# ch340_usb.net
KiCad netlist of a schematic drawn in EAGLE
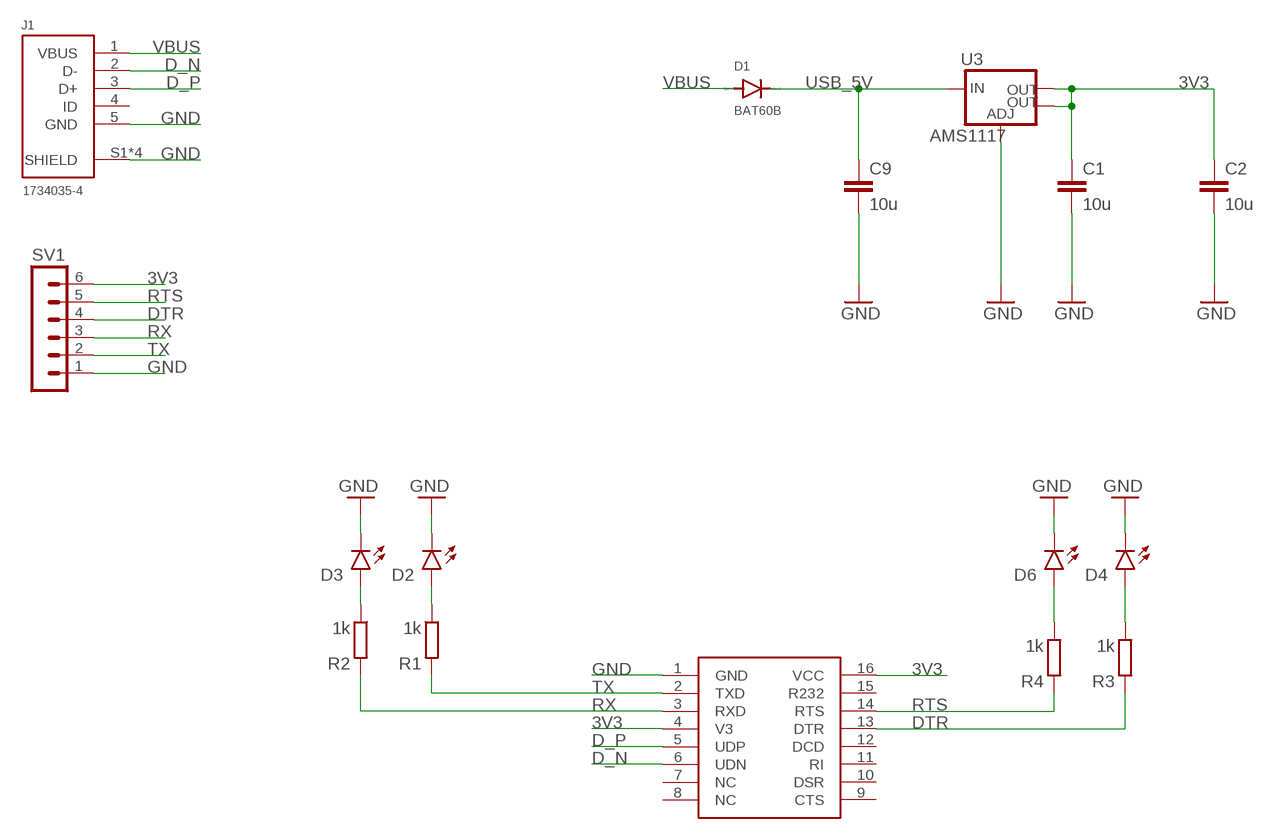
[diagram p0: schematic, sheet 1]

(export (version "E")
  (design (tool "Eeschema 10.0.6"))
  (components
    (comp (ref "C1")
      (value "10u")
      (footprint "eagle-import:C0805K")
      (libsource (lib "eagle-import") (part "C-EUC0805K"))
    )
    (comp (ref "C2")
      (value "10u")
      (footprint "eagle-import:C0805K")
      (libsource (lib "eagle-import") (part "C-EUC0805K"))
    )
    (comp (ref "C9")
      (value "10u")
      (footprint "eagle-import:C0805K")
      (libsource (lib "eagle-import") (part "C-EUC0805K"))
    )
    (comp (ref "D1")
      (value "BAT60B")
      (footprint "eagle-import:SOD123")
      (libsource (lib "eagle-import") (part "MBR0520LT"))
    )
    (comp (ref "D2")
      (value "PWR")
      (footprint "eagle-import:LED3MM")
      (fields (field (name "MF") "VISHAY SEMICONDUCTOR"))
      (libsource (lib "eagle-import") (part "TLLG4400"))
    )
    (comp (ref "D3")
      (value "PWR")
      (footprint "eagle-import:LED3MM")
      (fields (field (name "MF") "VISHAY SEMICONDUCTOR"))
      (libsource (lib "eagle-import") (part "TLLG4400"))
    )
    (comp (ref "D4")
      (value "PWR")
      (footprint "eagle-import:LED3MM")
      (fields (field (name "MF") "VISHAY SEMICONDUCTOR"))
      (libsource (lib "eagle-import") (part "TLLG4400"))
    )
    (comp (ref "D6")
      (value "PWR")
      (footprint "eagle-import:LED3MM")
      (fields (field (name "MF") "VISHAY SEMICONDUCTOR"))
      (libsource (lib "eagle-import") (part "TLLG4400"))
    )
    (comp (ref "J1")
      (value "1734035-4")
      (footprint "eagle-import:1734035-4")
      (fields
        (field (name "DIGIKEY_PARTNO") "A121554TR-ND")
        (field (name "MANUFACTURER") "TE Connectivity AMP Connectors")
        (field (name "CREATED_BY") "PCBLayout.com")
      )
      (libsource (lib "eagle-import") (part "1734035-4"))
    )
    (comp (ref "R1")
      (value "1k")
      (footprint "eagle-import:R0805")
      (libsource (lib "eagle-import") (part "R-EU_R0805"))
    )
    (comp (ref "R2")
      (value "1k")
      (footprint "eagle-import:R0805")
      (libsource (lib "eagle-import") (part "R-EU_R0805"))
    )
    (comp (ref "R3")
      (value "1k")
      (footprint "eagle-import:R0805")
      (libsource (lib "eagle-import") (part "R-EU_R0805"))
    )
    (comp (ref "R4")
      (value "1k")
      (footprint "eagle-import:R0805")
      (libsource (lib "eagle-import") (part "R-EU_R0805"))
    )
    (comp (ref "SV1")
      (value "MA06-1")
      (footprint "eagle-import:MA06-1")
      (libsource (lib "eagle-import") (part "MA06-1"))
    )
    (comp (ref "U$1")
      (value "CH340")
      (footprint "eagle-import:SOP16")
      (libsource (lib "eagle-import") (part "CH340"))
    )
    (comp (ref "U3")
      (value "AMS1117")
      (footprint "eagle-import:SOT223")
      (libsource (lib "eagle-import") (part "V_REG_LM1117SOT223"))
    )
  )
  (nets
    (net (code "1") (name "/3V3") (class "Default")
      (node (ref "C1") (pin "1") (pinfunction "1_1") (pintype "passive"))
      (node (ref "C2") (pin "1") (pinfunction "1_1") (pintype "passive"))
      (node (ref "SV1") (pin "6") (pinfunction "6_6") (pintype "passive"))
      (node (ref "U$1") (pin "16") (pinfunction "VCC_16") (pintype "bidirectional"))
      (node (ref "U$1") (pin "4") (pinfunction "V3_4") (pintype "bidirectional"))
      (node (ref "U3") (pin "2") (pinfunction "OUT_2") (pintype "output"))
      (node (ref "U3") (pin "4") (pinfunction "OUT_4") (pintype "output"))
    )
    (net (code "2") (name "/DTR") (class "Default")
      (node (ref "R3") (pin "2") (pinfunction "2_2") (pintype "passive"))
      (node (ref "SV1") (pin "4") (pinfunction "4_4") (pintype "passive"))
      (node (ref "U$1") (pin "13") (pinfunction "DTR_13") (pintype "bidirectional"))
    )
    (net (code "3") (name "/D_N") (class "Default")
      (node (ref "J1") (pin "2") (pinfunction "D-_2") (pintype "passive"))
      (node (ref "U$1") (pin "6") (pinfunction "UDN_6") (pintype "bidirectional"))
    )
    (net (code "4") (name "/D_P") (class "Default")
      (node (ref "J1") (pin "3") (pinfunction "D+_3") (pintype "passive"))
      (node (ref "U$1") (pin "5") (pinfunction "UDP_5") (pintype "bidirectional"))
    )
    (net (code "5") (name "/RTS") (class "Default")
      (node (ref "R4") (pin "2") (pinfunction "2_2") (pintype "passive"))
      (node (ref "SV1") (pin "5") (pinfunction "5_5") (pintype "passive"))
      (node (ref "U$1") (pin "14") (pinfunction "RTS_14") (pintype "bidirectional"))
    )
    (net (code "6") (name "/RX") (class "Default")
      (node (ref "R2") (pin "2") (pinfunction "2_2") (pintype "passive"))
      (node (ref "SV1") (pin "3") (pinfunction "3_3") (pintype "passive"))
      (node (ref "U$1") (pin "3") (pinfunction "RXD_3") (pintype "bidirectional"))
    )
    (net (code "7") (name "/TX") (class "Default")
      (node (ref "R1") (pin "2") (pinfunction "2_2") (pintype "passive"))
      (node (ref "SV1") (pin "2") (pinfunction "2_2") (pintype "passive"))
      (node (ref "U$1") (pin "2") (pinfunction "TXD_2") (pintype "bidirectional"))
    )
    (net (code "8") (name "/USB_5V") (class "Default")
      (node (ref "C9") (pin "1") (pinfunction "1_1") (pintype "passive"))
      (node (ref "D1") (pin "C") (pinfunction "C_C") (pintype "passive"))
      (node (ref "U3") (pin "3") (pinfunction "IN_3") (pintype "input"))
    )
    (net (code "9") (name "/VBUS") (class "Default")
      (node (ref "D1") (pin "A") (pinfunction "A_A") (pintype "passive"))
      (node (ref "J1") (pin "1") (pinfunction "VBUS_1") (pintype "passive"))
    )
    (net (code "10") (name "GND") (class "Default")
      (node (ref "C1") (pin "2") (pinfunction "2_2") (pintype "passive"))
      (node (ref "C2") (pin "2") (pinfunction "2_2") (pintype "passive"))
      (node (ref "C9") (pin "2") (pinfunction "2_2") (pintype "passive"))
      (node (ref "D2") (pin "K") (pinfunction "C_K") (pintype "passive"))
      (node (ref "D3") (pin "K") (pinfunction "C_K") (pintype "passive"))
      (node (ref "D4") (pin "K") (pinfunction "C_K") (pintype "passive"))
      (node (ref "D6") (pin "K") (pinfunction "C_K") (pintype "passive"))
      (node (ref "J1") (pin "5") (pinfunction "GND_5") (pintype "passive"))
      (node (ref "J1") (pin "S1") (pinfunction "SHIELD_S1") (pintype "power_in"))
      (node (ref "J1") (pin "S2") (pinfunction "SHIELD_S2") (pintype "power_in"))
      (node (ref "J1") (pin "S3") (pinfunction "SHIELD_S3") (pintype "power_in"))
      (node (ref "J1") (pin "S4") (pinfunction "SHIELD_S4") (pintype "power_in"))
      (node (ref "SV1") (pin "1") (pinfunction "1_1") (pintype "passive"))
      (node (ref "U$1") (pin "1") (pinfunction "GND_1") (pintype "bidirectional"))
      (node (ref "U3") (pin "1") (pinfunction "ADJ_1") (pintype "input"))
    )
    (net (code "11") (name "Net-(D2-PadA)") (class "Default")
      (node (ref "D2") (pin "A") (pinfunction "A_A") (pintype "passive"))
      (node (ref "R1") (pin "1") (pinfunction "1_1") (pintype "passive"))
    )
    (net (code "12") (name "Net-(D3-PadA)") (class "Default")
      (node (ref "D3") (pin "A") (pinfunction "A_A") (pintype "passive"))
      (node (ref "R2") (pin "1") (pinfunction "1_1") (pintype "passive"))
    )
    (net (code "13") (name "Net-(D4-PadA)") (class "Default")
      (node (ref "D4") (pin "A") (pinfunction "A_A") (pintype "passive"))
      (node (ref "R3") (pin "1") (pinfunction "1_1") (pintype "passive"))
    )
    (net (code "14") (name "Net-(D6-PadA)") (class "Default")
      (node (ref "D6") (pin "A") (pinfunction "A_A") (pintype "passive"))
      (node (ref "R4") (pin "1") (pinfunction "1_1") (pintype "passive"))
    )
    (net (code "15") (name "unconnected-(J1-ID-Pad4)") (class "Default")
      (node (ref "J1") (pin "4") (pinfunction "ID_4") (pintype "passive"))
    )
    (net (code "16") (name "unconnected-(U$1-CTS-Pad9)") (class "Default")
      (node (ref "U$1") (pin "9") (pinfunction "CTS_9") (pintype "bidirectional"))
    )
    (net (code "17") (name "unconnected-(U$1-DCD-Pad12)") (class "Default")
      (node (ref "U$1") (pin "12") (pinfunction "DCD_12") (pintype "bidirectional"))
    )
    (net (code "18") (name "unconnected-(U$1-DSR-Pad10)") (class "Default")
      (node (ref "U$1") (pin "10") (pinfunction "DSR_10") (pintype "bidirectional"))
    )
    (net (code "19") (name "unconnected-(U$1-NC-Pad7)") (class "Default")
      (node (ref "U$1") (pin "7") (pinfunction "NC_7") (pintype "bidirectional"))
    )
    (net (code "20") (name "unconnected-(U$1-NC-Pad8)") (class "Default")
      (node (ref "U$1") (pin "8") (pinfunction "NC_8") (pintype "bidirectional"))
    )
    (net (code "21") (name "unconnected-(U$1-R232-Pad15)") (class "Default")
      (node (ref "U$1") (pin "15") (pinfunction "R232_15") (pintype "bidirectional"))
    )
    (net (code "22") (name "unconnected-(U$1-RI-Pad11)") (class "Default")
      (node (ref "U$1") (pin "11") (pinfunction "RI_11") (pintype "bidirectional"))
    )
  )
)
